# MUSIC_L_VOICE_R_2026-11-20.net
KiCad netlist of a schematic drawn in EasyEDA Pro
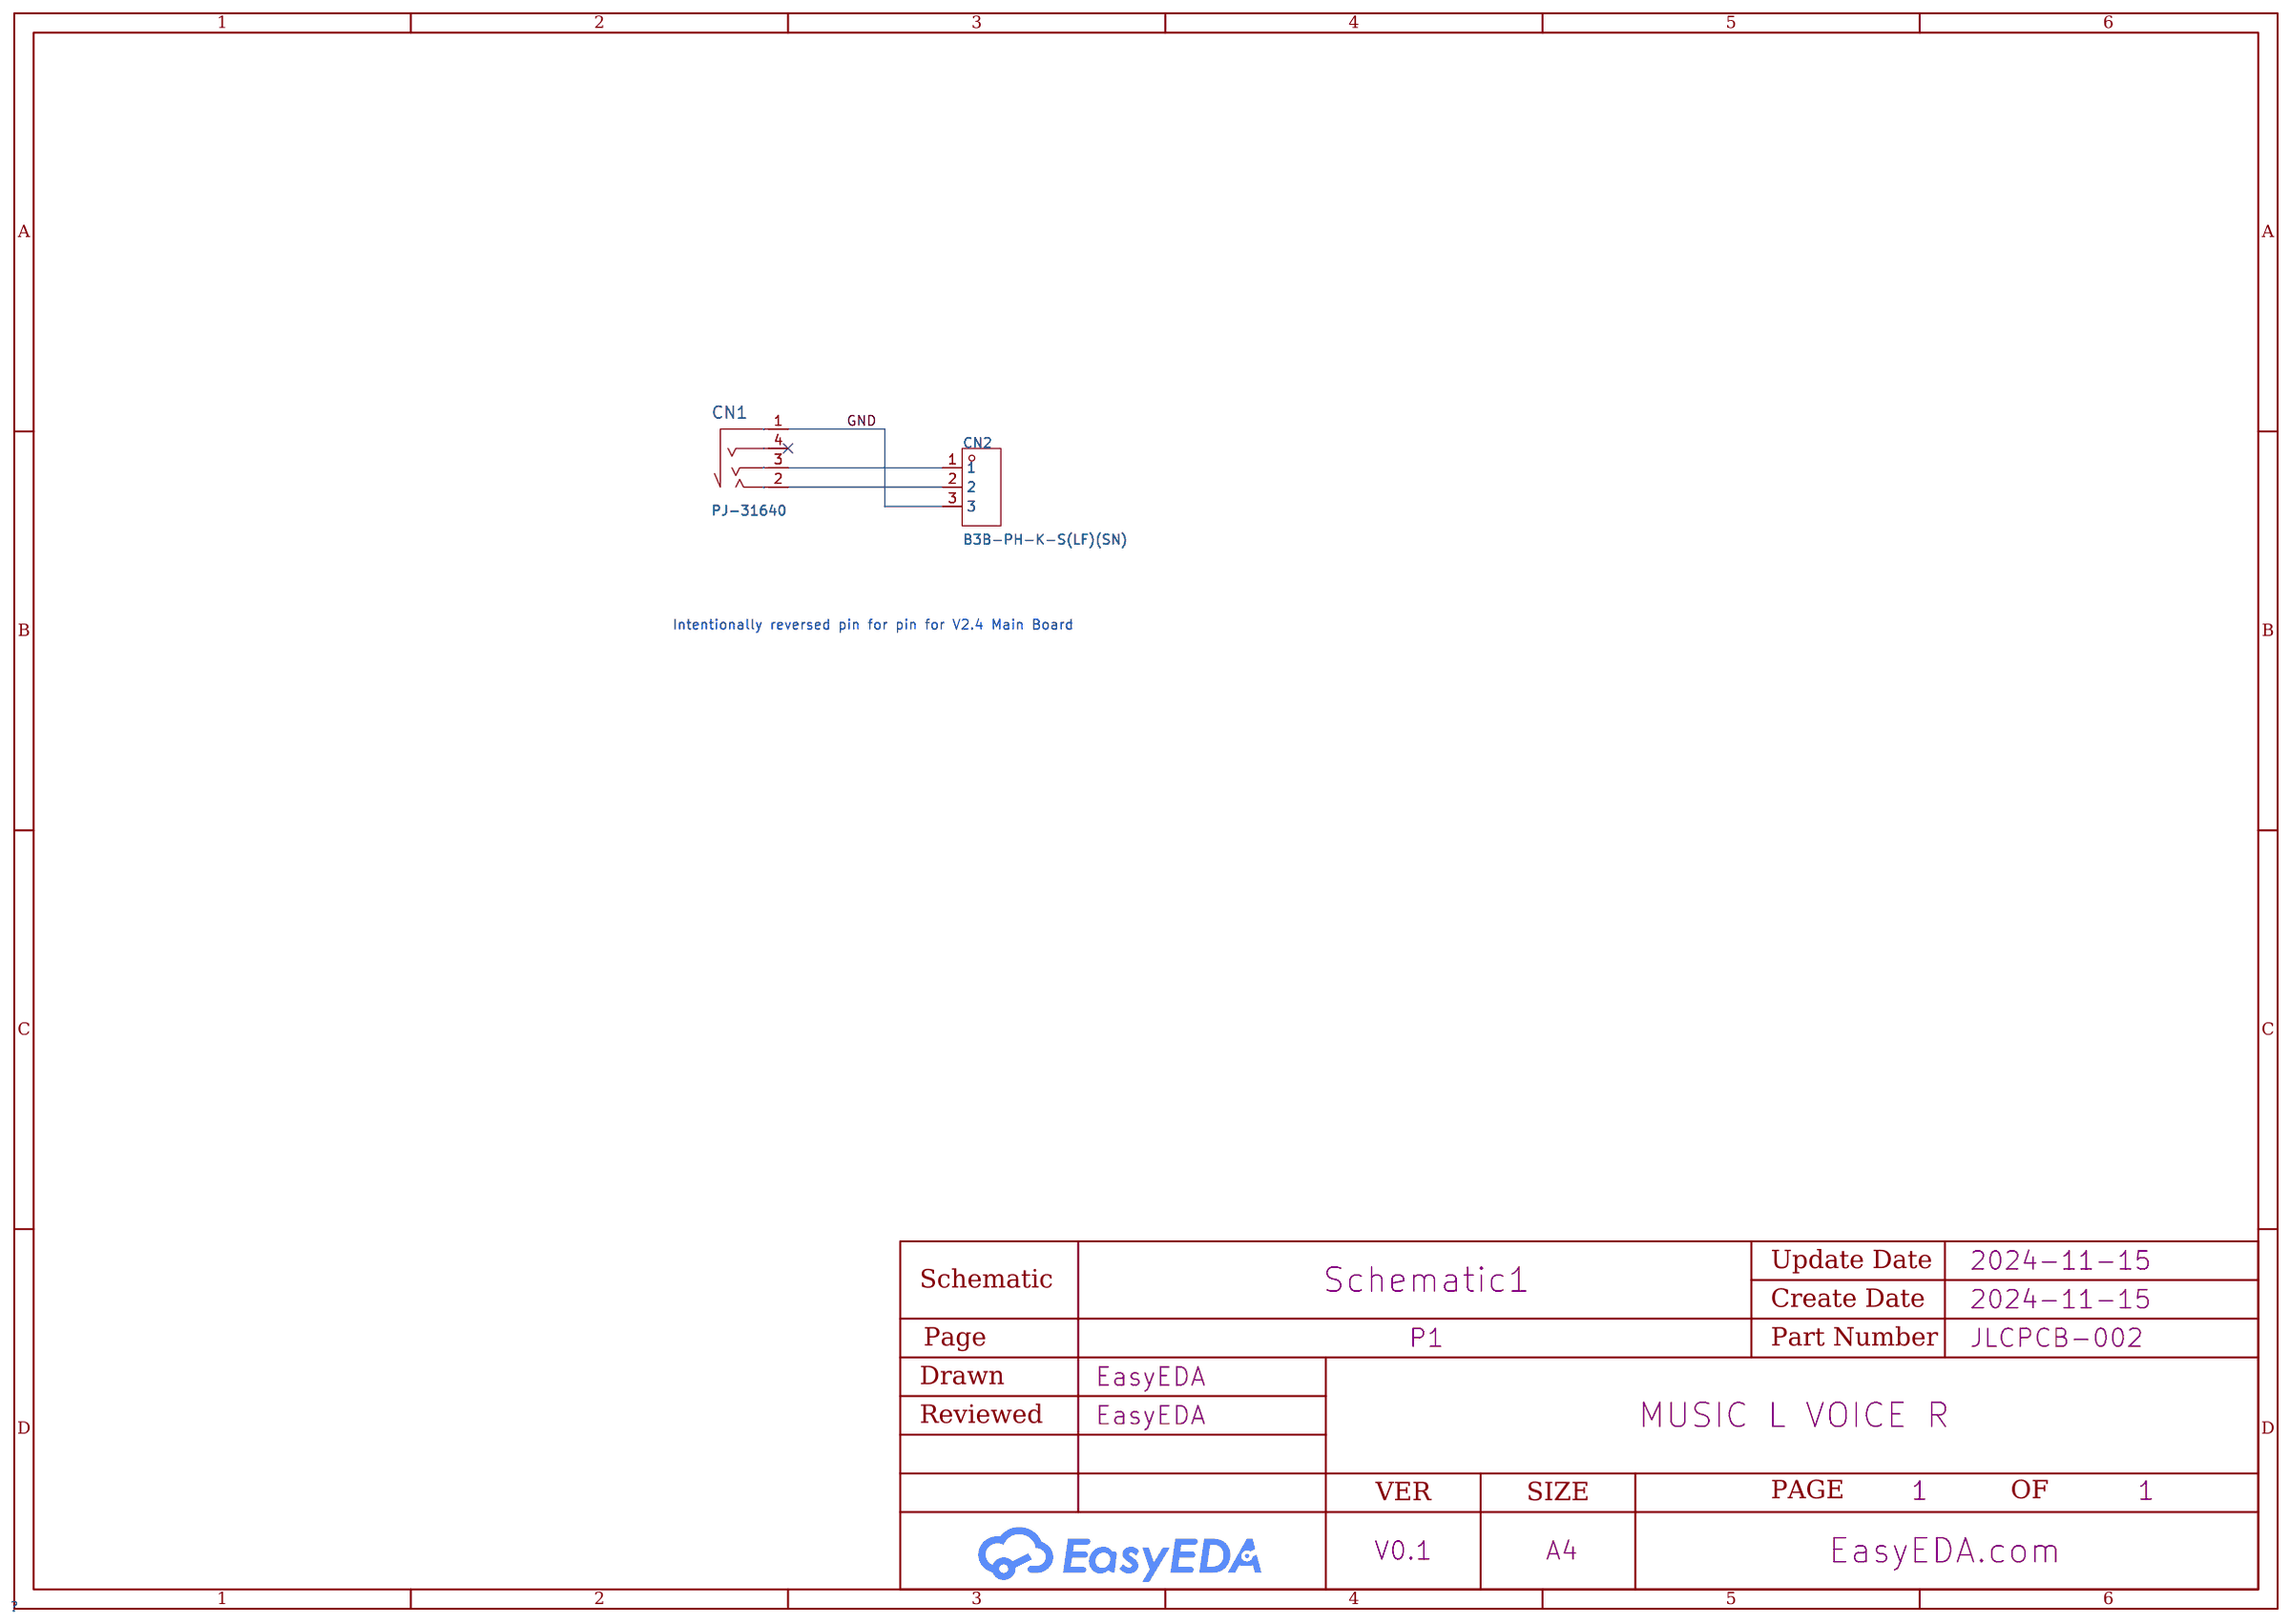
[diagram p0: schematic sheet]

(export (version "E")
  (design (tool "Eeschema 10.0.6"))
  (components
    (comp (ref "CN1")
      (value "PJ-31640")
      (footprint "easyedapro:AUDIO-TH_XKB_PJ-31640")
      (fields (field (name "Manufacturer") "XKB Connectivity(中国星坤)"))
      (libsource (lib "easyedapro") (part "PJ-31640"))
    )
    (comp (ref "CN2")
      (value "B3B-PH-K-S(LF)(SN)")
      (footprint "easyedapro:CONN-TH_B3B-PH-K-S")
      (fields (field (name "Manufacturer") "JST"))
      (libsource (lib "easyedapro") (part "B3B-PH-K-S(LF)(SN)"))
    )
  )
  (nets
    (net (code "1") (name "/GND") (class "Default")
      (node (ref "CN1") (pin "1") (pinfunction "1_1") (pintype "input"))
      (node (ref "CN2") (pin "3") (pinfunction "3_3") (pintype "unspecified"))
    )
    (net (code "2") (name "Net-(CN1-Pad2)") (class "Default")
      (node (ref "CN1") (pin "2") (pinfunction "2_2") (pintype "input"))
      (node (ref "CN2") (pin "2") (pinfunction "2_2") (pintype "unspecified"))
    )
    (net (code "3") (name "Net-(CN1-Pad3)") (class "Default")
      (node (ref "CN1") (pin "3") (pinfunction "3_3") (pintype "input"))
      (node (ref "CN2") (pin "1") (pinfunction "1_1") (pintype "unspecified"))
    )
    (net (code "4") (name "unconnected-(CN1-Pad4)") (class "Default")
      (node (ref "CN1") (pin "4") (pinfunction "4_4") (pintype "input+no_connect"))
    )
  )
)
